# CP2102N_USB-to-UART_Bridge_V3_0.net
KiCad netlist of a schematic drawn in Altium Designer
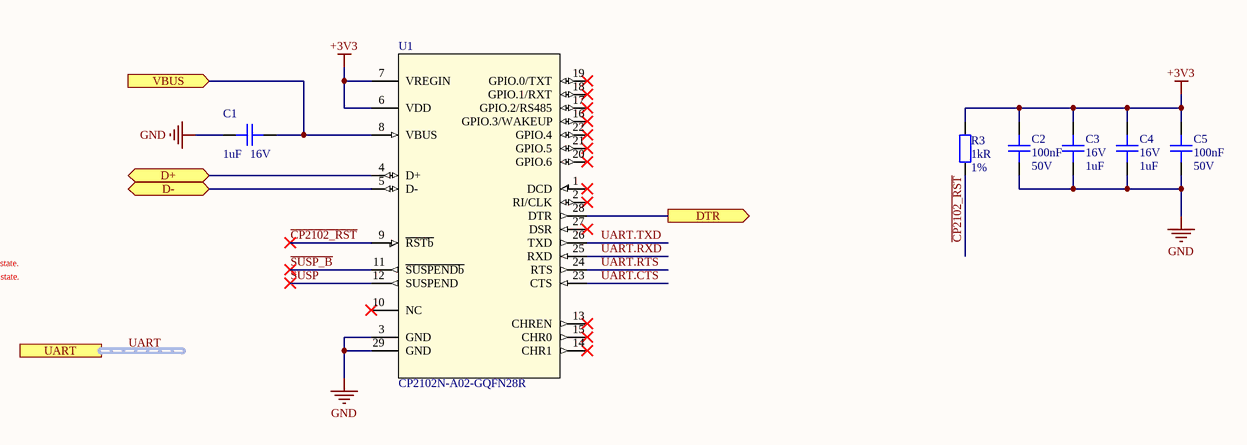
[diagram p0: CP2102N_USB-to-UART_Bridge_V3.0.SchDoc]

(export (version "E")
  (design (tool "Eeschema 10.0.6"))
  (components
    (comp (ref "C1")
      (value "CAP CER 1UF 16V X5R 0402")
      (footprint "C0402")
      (description "1µF ±10% 16V Ceramic Capacitor X5R 0402 (1005 Metric)")
      (fields
        (field (name "MANUFACTURER PART NUMBER") "CC0402KRX5R7BB105")
        (field (name "MANUFACTURER") "Yageo")
        (field (name "VOLTAGE RATING") "16V")
        (field (name "CAPACITANCE") "1uF")
      )
      (libsource (lib "capacitors_smd") (part "CAP CER 1UF 16V X5R 0402"))
    )
    (comp (ref "C2")
      (value "CAP CER 0.1UF 50V X7R 0402")
      (footprint "C0402")
      (description "0.1µF ±10% 50V Ceramic Capacitor X7R 0402 (1005 Metric)")
      (fields
        (field (name "MANUFACTURER PART NUMBER") "CGA2B3X7R1H104K050BB")
        (field (name "MANUFACTURER") "TDK")
        (field (name "CAPACITANCE") "100nF")
        (field (name "VOLTAGE") "50V")
      )
      (libsource (lib "capacitors_smd") (part "CAP CER 0.1UF 50V X7R 0402"))
    )
    (comp (ref "C3")
      (value "CAP CER 1UF 16V X5R 0402")
      (footprint "C0402")
      (description "1µF ±10% 16V Ceramic Capacitor X5R 0402 (1005 Metric)")
      (fields
        (field (name "MANUFACTURER") "Yageo")
        (field (name "MANUFACTURER PART NUMBER") "CC0402KRX5R7BB105")
        (field (name "VOLTAGE RATING") "16V")
        (field (name "CAPACITANCE") "1uF")
      )
      (libsource (lib "capacitors_smd") (part "CAP CER 1UF 16V X5R 0402"))
    )
    (comp (ref "C4")
      (value "CAP CER 1UF 16V X5R 0402")
      (footprint "C0402")
      (description "1µF ±10% 16V Ceramic Capacitor X5R 0402 (1005 Metric)")
      (fields
        (field (name "MANUFACTURER") "Yageo")
        (field (name "MANUFACTURER PART NUMBER") "CC0402KRX5R7BB105")
        (field (name "VOLTAGE RATING") "16V")
        (field (name "CAPACITANCE") "1uF")
      )
      (libsource (lib "capacitors_smd") (part "CAP CER 1UF 16V X5R 0402"))
    )
    (comp (ref "C5")
      (value "CAP CER 0.1UF 50V X7R 0402")
      (footprint "C0402")
      (description "0.1µF ±10% 50V Ceramic Capacitor X7R 0402 (1005 Metric)")
      (fields
        (field (name "MANUFACTURER PART NUMBER") "CGA2B3X7R1H104K050BB")
        (field (name "MANUFACTURER") "TDK")
        (field (name "CAPACITANCE") "100nF")
        (field (name "VOLTAGE") "50V")
      )
      (libsource (lib "capacitors_smd") (part "CAP CER 0.1UF 50V X7R 0402"))
    )
    (comp (ref "R3")
      (value "RES SMD 1K OHM 1% 1/16W 0402")
      (footprint "R0402")
      (description "1 kOhms ±1% 0.063W, 1/16W Chip Resistor 0402 (1005 Metric) Moisture Resistant Thick Film")
      (fields
        (field (name "MANUFACTURER PART NUMBER") "RC0402FR-071KL")
        (field (name "MANUFACTURER") "Yageo")
        (field (name "RESISTANCE") "1kR")
        (field (name "TOLERANCE") "1%")
      )
      (libsource (lib "resistors_smd") (part "RES SMD 1K OHM 1% 1/16W 0402"))
    )
    (comp (ref "U1")
      (value "CP2102N-A02-GQFN28R")
      (footprint "QFN28_5X5")
      (description "USB Bridge, USB to UART USB 2.0 UART Interface 28-QFN (5x5)")
      (fields (field (name "MANUFACTURER") "Silicon Labs"))
      (libsource (lib "BLDC_Moto_Driver") (part "IC CP2102N USB TO UART BRIDGE QFN28"))
    )
  )
  (nets
    (net (code "2") (name "+3V3") (class "Default")
      (node (ref "C2") (pin "2") (pinfunction "2_2") (pintype "passive"))
      (node (ref "C3") (pin "2") (pinfunction "2_2") (pintype "passive"))
      (node (ref "C4") (pin "2") (pinfunction "2_2") (pintype "passive"))
      (node (ref "C5") (pin "2") (pinfunction "2_2") (pintype "passive"))
      (node (ref "R3") (pin "1") (pinfunction "1_1") (pintype "passive"))
      (node (ref "U1") (pin "6") (pinfunction "VDD_6") (pintype "power_in"))
      (node (ref "U1") (pin "7") (pinfunction "VREGIN_7") (pintype "power_in"))
    )
    (net (code "3") (name "/CP2102_RST") (class "Default")
      (node (ref "R3") (pin "2") (pinfunction "2_2") (pintype "passive"))
      (node (ref "U1") (pin "9") (pinfunction "RSTb_9") (pintype "input"))
    )
    (net (code "4") (name "/D+") (class "Default")
      (node (ref "U1") (pin "4") (pinfunction "D+_4") (pintype "bidirectional"))
    )
    (net (code "5") (name "/D-") (class "Default")
      (node (ref "U1") (pin "5") (pinfunction "D-_5") (pintype "bidirectional"))
    )
    (net (code "6") (name "/DTR") (class "Default")
      (node (ref "U1") (pin "28") (pinfunction "DTR_28") (pintype "output"))
    )
    (net (code "7") (name "/SUSP") (class "Default")
      (node (ref "U1") (pin "12") (pinfunction "SUSPEND_12") (pintype "output+no_connect"))
    )
    (net (code "8") (name "/SUSP_B") (class "Default")
      (node (ref "U1") (pin "11") (pinfunction "SUSPENDb_11") (pintype "output+no_connect"))
    )
    (net (code "9") (name "/UART.CTS") (class "Default")
      (node (ref "U1") (pin "23") (pinfunction "CTS_23") (pintype "input"))
    )
    (net (code "10") (name "/UART.RTS") (class "Default")
      (node (ref "U1") (pin "24") (pinfunction "RTS_24") (pintype "output"))
    )
    (net (code "11") (name "/UART.RXD") (class "Default")
      (node (ref "U1") (pin "25") (pinfunction "RXD_25") (pintype "input"))
    )
    (net (code "12") (name "/UART.TXD") (class "Default")
      (node (ref "U1") (pin "26") (pinfunction "TXD_26") (pintype "output"))
    )
    (net (code "13") (name "/VBUS") (class "Default")
      (node (ref "C1") (pin "2") (pinfunction "2_2") (pintype "passive"))
      (node (ref "U1") (pin "8") (pinfunction "VBUS_8") (pintype "input"))
    )
    (net (code "15") (name "GND") (class "Default")
      (node (ref "C1") (pin "1") (pinfunction "1_1") (pintype "passive"))
      (node (ref "C2") (pin "1") (pinfunction "1_1") (pintype "passive"))
      (node (ref "C3") (pin "1") (pinfunction "1_1") (pintype "passive"))
      (node (ref "C4") (pin "1") (pinfunction "1_1") (pintype "passive"))
      (node (ref "C5") (pin "1") (pinfunction "1_1") (pintype "passive"))
      (node (ref "U1") (pin "29") (pinfunction "GND_29") (pintype "power_in"))
      (node (ref "U1") (pin "3") (pinfunction "GND_3") (pintype "power_in"))
    )
    (net (code "16") (name "unconnected-(U1-CHR0-Pad15)") (class "Default")
      (node (ref "U1") (pin "15") (pinfunction "CHR0_15") (pintype "output+no_connect"))
    )
    (net (code "17") (name "unconnected-(U1-CHR1-Pad14)") (class "Default")
      (node (ref "U1") (pin "14") (pinfunction "CHR1_14") (pintype "output+no_connect"))
    )
    (net (code "18") (name "unconnected-(U1-CHREN-Pad13)") (class "Default")
      (node (ref "U1") (pin "13") (pinfunction "CHREN_13") (pintype "output+no_connect"))
    )
    (net (code "19") (name "unconnected-(U1-DCD-Pad1)") (class "Default")
      (node (ref "U1") (pin "1") (pinfunction "DCD_1") (pintype "input+no_connect"))
    )
    (net (code "20") (name "unconnected-(U1-DSR-Pad27)") (class "Default")
      (node (ref "U1") (pin "27") (pinfunction "DSR_27") (pintype "input+no_connect"))
    )
    (net (code "21") (name "unconnected-(U1-GPIO.0{slash}TXT-Pad19)") (class "Default")
      (node (ref "U1") (pin "19") (pinfunction "GPIO.0/TXT_19") (pintype "bidirectional+no_connect"))
    )
    (net (code "22") (name "unconnected-(U1-GPIO.1{slash}RXT-Pad18)") (class "Default")
      (node (ref "U1") (pin "18") (pinfunction "GPIO.1/RXT_18") (pintype "bidirectional+no_connect"))
    )
    (net (code "23") (name "unconnected-(U1-GPIO.2{slash}RS485-Pad17)") (class "Default")
      (node (ref "U1") (pin "17") (pinfunction "GPIO.2/RS485_17") (pintype "bidirectional+no_connect"))
    )
    (net (code "24") (name "unconnected-(U1-GPIO.3{slash}WAKEUP-Pad16)") (class "Default")
      (node (ref "U1") (pin "16") (pinfunction "GPIO.3/WAKEUP_16") (pintype "bidirectional+no_connect"))
    )
    (net (code "25") (name "unconnected-(U1-GPIO.4-Pad22)") (class "Default")
      (node (ref "U1") (pin "22") (pinfunction "GPIO.4_22") (pintype "bidirectional+no_connect"))
    )
    (net (code "26") (name "unconnected-(U1-GPIO.5-Pad21)") (class "Default")
      (node (ref "U1") (pin "21") (pinfunction "GPIO.5_21") (pintype "bidirectional+no_connect"))
    )
    (net (code "27") (name "unconnected-(U1-GPIO.6-Pad20)") (class "Default")
      (node (ref "U1") (pin "20") (pinfunction "GPIO.6_20") (pintype "bidirectional+no_connect"))
    )
    (net (code "28") (name "unconnected-(U1-NC-Pad10)") (class "Default")
      (node (ref "U1") (pin "10") (pinfunction "NC_10") (pintype "passive+no_connect"))
    )
    (net (code "29") (name "unconnected-(U1-RI{slash}CLK-Pad2)") (class "Default")
      (node (ref "U1") (pin "2") (pinfunction "RI/CLK_2") (pintype "bidirectional+no_connect"))
    )
  )
)
